# ADAPTADOR.net
KiCad netlist of a schematic drawn in Altium Designer
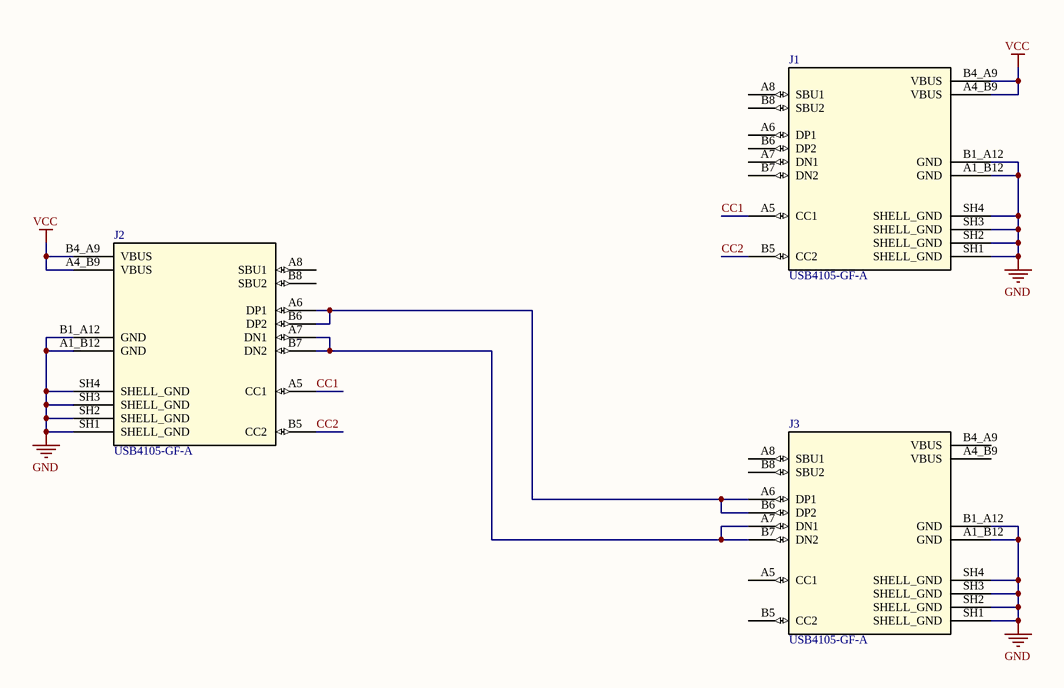
[diagram p0: ADAPTADOR.SchDoc]

(export (version "E")
  (design (tool "Eeschema 10.0.6"))
  (components
    (comp (ref "J1")
      (value "CONN RCP USB2.0 TYP C 24P SMD RA")
      (footprint "GCT_USB4105-GF-A")
      (description "CONN RCP USB2.0 TYP C 24P SMD RA PN: USB4105-GF-A")
      (fields (field (name "MF") "{'manufacturer': u'GCT'}") (field (name "PN") "USB4105-GF-A"))
      (libsource (lib "Schlib2") (part "CONN RCP USB2.0 TYP C 24P SMD RA"))
    )
    (comp (ref "J2")
      (value "CONN RCP USB2.0 TYP C 24P SMD RA")
      (footprint "GCT_USB4105-GF-A")
      (description "CONN RCP USB2.0 TYP C 24P SMD RA PN: USB4105-GF-A")
      (fields (field (name "MF") "{'manufacturer': u'GCT'}") (field (name "PN") "USB4105-GF-A"))
      (libsource (lib "") (part "CONN RCP USB2.0 TYP C 24P SMD RA_1"))
    )
    (comp (ref "J3")
      (value "CONN RCP USB2.0 TYP C 24P SMD RA")
      (footprint "GCT_USB4105-GF-A")
      (description "CONN RCP USB2.0 TYP C 24P SMD RA PN: USB4105-GF-A")
      (fields (field (name "MF") "{'manufacturer': u'GCT'}") (field (name "PN") "USB4105-GF-A"))
      (libsource (lib "Schlib2") (part "CONN RCP USB2.0 TYP C 24P SMD RA"))
    )
  )
  (nets
    (net (code "1") (name "/CC1") (class "Default")
      (node (ref "J1") (pin "A5") (pinfunction "CC1_A5") (pintype "bidirectional"))
      (node (ref "J2") (pin "A5") (pinfunction "CC1_A5") (pintype "bidirectional"))
    )
    (net (code "2") (name "/CC2") (class "Default")
      (node (ref "J1") (pin "B5") (pinfunction "CC2_B5") (pintype "bidirectional"))
      (node (ref "J2") (pin "B5") (pinfunction "CC2_B5") (pintype "bidirectional"))
    )
    (net (code "3") (name "GND") (class "Default")
      (node (ref "J1") (pin "A1_B12") (pinfunction "GND_A1_B12") (pintype "power_in"))
      (node (ref "J1") (pin "B1_A12") (pinfunction "GND_B1_A12") (pintype "power_in"))
      (node (ref "J1") (pin "SH1") (pinfunction "SHELL_GND_SH1") (pintype "power_in"))
      (node (ref "J1") (pin "SH2") (pinfunction "SHELL_GND_SH2") (pintype "power_in"))
      (node (ref "J1") (pin "SH3") (pinfunction "SHELL_GND_SH3") (pintype "power_in"))
      (node (ref "J1") (pin "SH4") (pinfunction "SHELL_GND_SH4") (pintype "power_in"))
      (node (ref "J2") (pin "A1_B12") (pinfunction "GND_A1_B12") (pintype "power_in"))
      (node (ref "J2") (pin "B1_A12") (pinfunction "GND_B1_A12") (pintype "power_in"))
      (node (ref "J2") (pin "SH1") (pinfunction "SHELL_GND_SH1") (pintype "power_in"))
      (node (ref "J2") (pin "SH2") (pinfunction "SHELL_GND_SH2") (pintype "power_in"))
      (node (ref "J2") (pin "SH3") (pinfunction "SHELL_GND_SH3") (pintype "power_in"))
      (node (ref "J2") (pin "SH4") (pinfunction "SHELL_GND_SH4") (pintype "power_in"))
      (node (ref "J3") (pin "A1_B12") (pinfunction "GND_A1_B12") (pintype "power_in"))
      (node (ref "J3") (pin "B1_A12") (pinfunction "GND_B1_A12") (pintype "power_in"))
      (node (ref "J3") (pin "SH1") (pinfunction "SHELL_GND_SH1") (pintype "power_in"))
      (node (ref "J3") (pin "SH2") (pinfunction "SHELL_GND_SH2") (pintype "power_in"))
      (node (ref "J3") (pin "SH3") (pinfunction "SHELL_GND_SH3") (pintype "power_in"))
      (node (ref "J3") (pin "SH4") (pinfunction "SHELL_GND_SH4") (pintype "power_in"))
    )
    (net (code "4") (name "Net-(J2-DN1)") (class "Default")
      (node (ref "J2") (pin "A7") (pinfunction "DN1_A7") (pintype "bidirectional"))
      (node (ref "J2") (pin "B7") (pinfunction "DN2_B7") (pintype "bidirectional"))
      (node (ref "J3") (pin "A7") (pinfunction "DN1_A7") (pintype "bidirectional"))
      (node (ref "J3") (pin "B7") (pinfunction "DN2_B7") (pintype "bidirectional"))
    )
    (net (code "5") (name "Net-(J2-DP1)") (class "Default")
      (node (ref "J2") (pin "A6") (pinfunction "DP1_A6") (pintype "bidirectional"))
      (node (ref "J2") (pin "B6") (pinfunction "DP2_B6") (pintype "bidirectional"))
      (node (ref "J3") (pin "A6") (pinfunction "DP1_A6") (pintype "bidirectional"))
      (node (ref "J3") (pin "B6") (pinfunction "DP2_B6") (pintype "bidirectional"))
    )
    (net (code "6") (name "VCC") (class "Default")
      (node (ref "J1") (pin "A4_B9") (pinfunction "VBUS_A4_B9") (pintype "power_in"))
      (node (ref "J1") (pin "B4_A9") (pinfunction "VBUS_B4_A9") (pintype "power_in"))
      (node (ref "J2") (pin "A4_B9") (pinfunction "VBUS_A4_B9") (pintype "power_in"))
      (node (ref "J2") (pin "B4_A9") (pinfunction "VBUS_B4_A9") (pintype "power_in"))
    )
    (net (code "7") (name "unconnected-(J1-DN1-PadA7)") (class "Default")
      (node (ref "J1") (pin "A7") (pinfunction "DN1_A7") (pintype "bidirectional"))
    )
    (net (code "8") (name "unconnected-(J1-DN2-PadB7)") (class "Default")
      (node (ref "J1") (pin "B7") (pinfunction "DN2_B7") (pintype "bidirectional"))
    )
    (net (code "9") (name "unconnected-(J1-DP1-PadA6)") (class "Default")
      (node (ref "J1") (pin "A6") (pinfunction "DP1_A6") (pintype "bidirectional"))
    )
    (net (code "10") (name "unconnected-(J1-DP2-PadB6)") (class "Default")
      (node (ref "J1") (pin "B6") (pinfunction "DP2_B6") (pintype "bidirectional"))
    )
    (net (code "11") (name "unconnected-(J1-SBU1-PadA8)") (class "Default")
      (node (ref "J1") (pin "A8") (pinfunction "SBU1_A8") (pintype "bidirectional"))
    )
    (net (code "12") (name "unconnected-(J1-SBU2-PadB8)") (class "Default")
      (node (ref "J1") (pin "B8") (pinfunction "SBU2_B8") (pintype "bidirectional"))
    )
    (net (code "13") (name "unconnected-(J2-SBU1-PadA8)") (class "Default")
      (node (ref "J2") (pin "A8") (pinfunction "SBU1_A8") (pintype "bidirectional"))
    )
    (net (code "14") (name "unconnected-(J2-SBU2-PadB8)") (class "Default")
      (node (ref "J2") (pin "B8") (pinfunction "SBU2_B8") (pintype "bidirectional"))
    )
    (net (code "15") (name "unconnected-(J3-CC1-PadA5)") (class "Default")
      (node (ref "J3") (pin "A5") (pinfunction "CC1_A5") (pintype "bidirectional"))
    )
    (net (code "16") (name "unconnected-(J3-CC2-PadB5)") (class "Default")
      (node (ref "J3") (pin "B5") (pinfunction "CC2_B5") (pintype "bidirectional"))
    )
    (net (code "17") (name "unconnected-(J3-SBU1-PadA8)") (class "Default")
      (node (ref "J3") (pin "A8") (pinfunction "SBU1_A8") (pintype "bidirectional"))
    )
    (net (code "18") (name "unconnected-(J3-SBU2-PadB8)") (class "Default")
      (node (ref "J3") (pin "B8") (pinfunction "SBU2_B8") (pintype "bidirectional"))
    )
    (net (code "19") (name "unconnected-(J3-VBUS-PadA4_B9)") (class "Default")
      (node (ref "J3") (pin "A4_B9") (pinfunction "VBUS_A4_B9") (pintype "power_in"))
    )
    (net (code "20") (name "unconnected-(J3-VBUS-PadB4_A9)") (class "Default")
      (node (ref "J3") (pin "B4_A9") (pinfunction "VBUS_B4_A9") (pintype "power_in"))
    )
  )
)
